# DDR3_Memory.net
KiCad netlist of a schematic drawn in Altium Designer
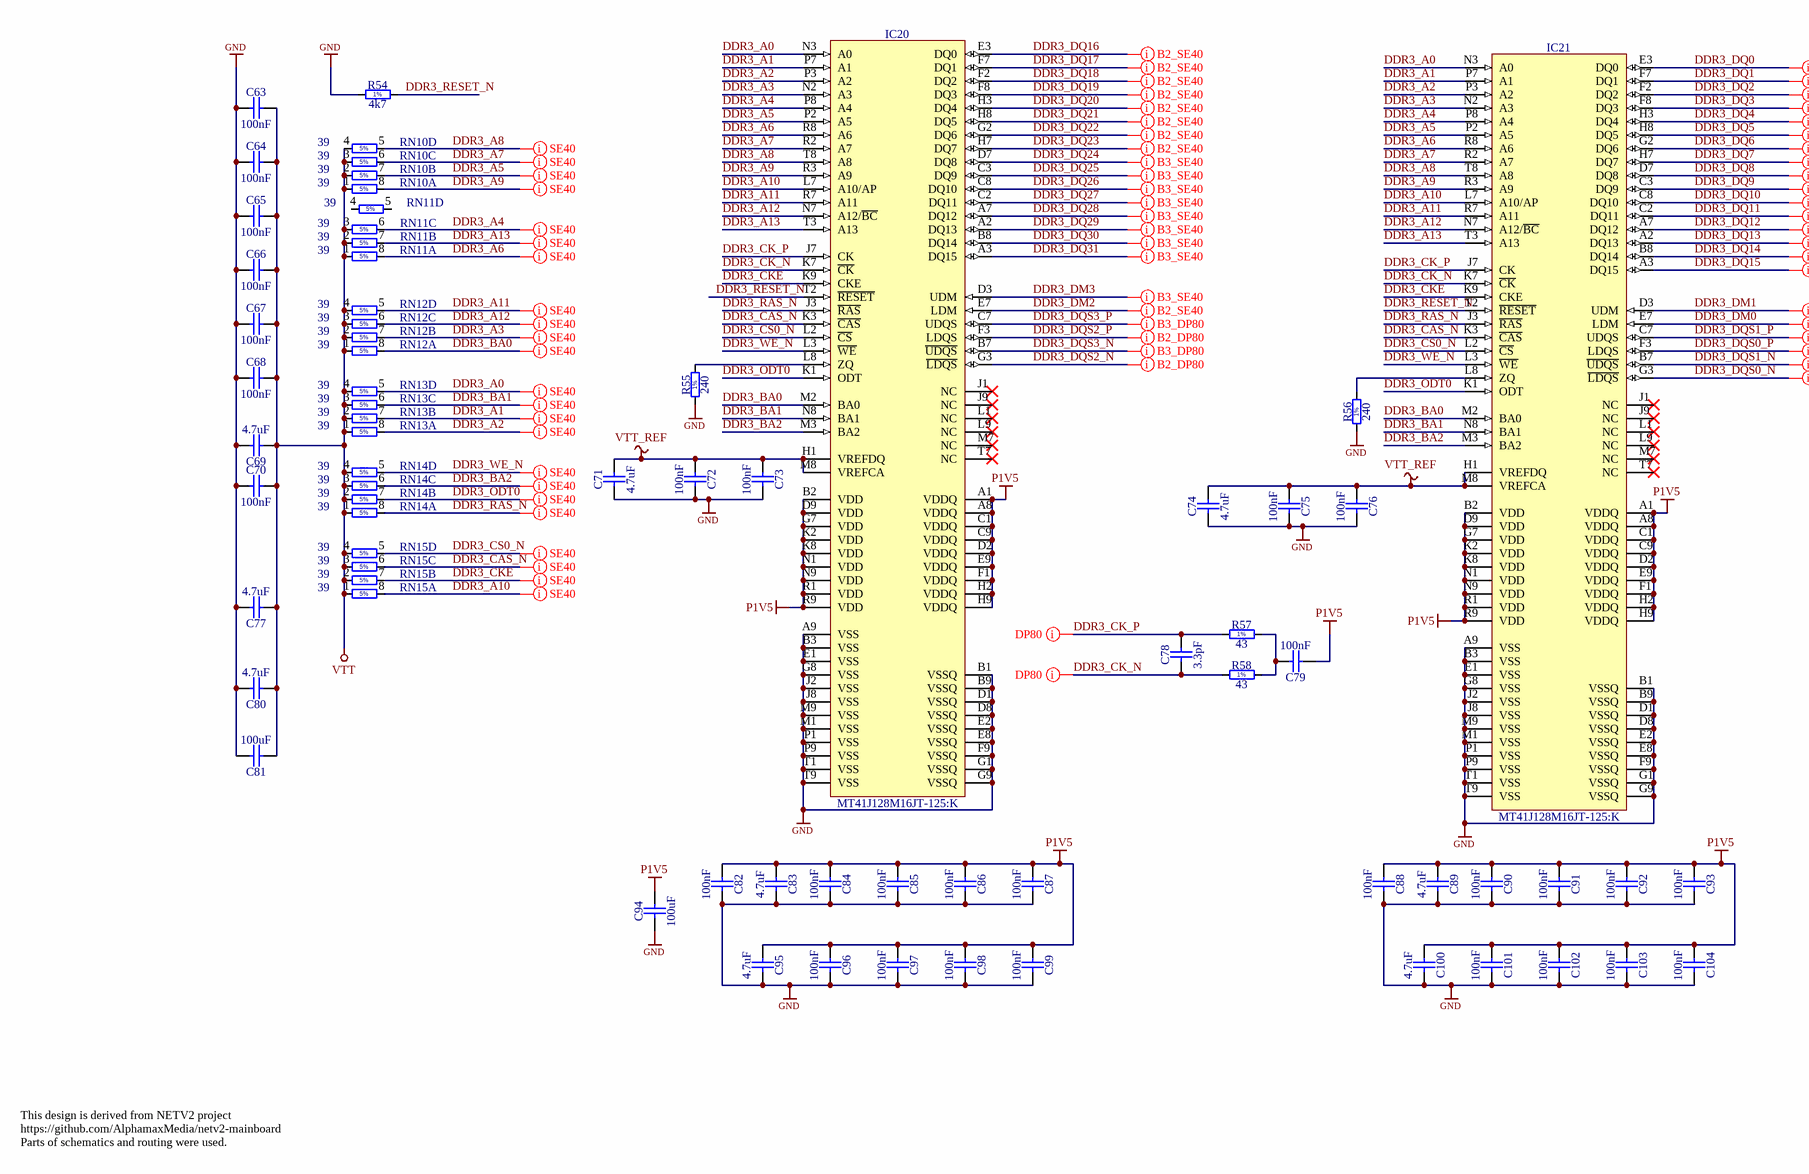
[diagram p0: DDR3_Memory.SchDoc]

(export (version "E")
  (design (tool "Eeschema 10.0.6"))
  (components
    (comp (ref "C63")
      (value "100nF")
      (footprint "CAPC0603X33N")
      (description "Non-polarised capacitor")
      (fields
        (field (name "PART NUMBER") "CC0201_100NF_6.3V_10%_X5R")
        (field (name "VOLTAGE") "6.3V")
        (field (name "AUTHOR") "CERN DEM JLC")
      )
      (libsource (lib "Capacitors") (part "Capacitor - non polarized"))
    )
    (comp (ref "C64")
      (value "100nF")
      (footprint "CAPC0603X33N")
      (description "Non-polarised capacitor")
      (fields
        (field (name "PART NUMBER") "CC0201_100NF_6.3V_10%_X5R")
        (field (name "VOLTAGE") "6.3V")
        (field (name "AUTHOR") "CERN DEM JLC")
      )
      (libsource (lib "Capacitors") (part "Capacitor - non polarized"))
    )
    (comp (ref "C65")
      (value "100nF")
      (footprint "CAPC0603X33N")
      (description "Non-polarised capacitor")
      (fields
        (field (name "PART NUMBER") "CC0201_100NF_6.3V_10%_X5R")
        (field (name "VOLTAGE") "6.3V")
        (field (name "AUTHOR") "CERN DEM JLC")
      )
      (libsource (lib "Capacitors") (part "Capacitor - non polarized"))
    )
    (comp (ref "C66")
      (value "100nF")
      (footprint "CAPC0603X33N")
      (description "Non-polarised capacitor")
      (fields
        (field (name "PART NUMBER") "CC0201_100NF_6.3V_10%_X5R")
        (field (name "VOLTAGE") "6.3V")
        (field (name "AUTHOR") "CERN DEM JLC")
      )
      (libsource (lib "Capacitors") (part "Capacitor - non polarized"))
    )
    (comp (ref "C67")
      (value "100nF")
      (footprint "CAPC0603X33N")
      (description "Non-polarised capacitor")
      (fields
        (field (name "PART NUMBER") "CC0201_100NF_6.3V_10%_X5R")
        (field (name "VOLTAGE") "6.3V")
        (field (name "AUTHOR") "CERN DEM JLC")
      )
      (libsource (lib "Capacitors") (part "Capacitor - non polarized"))
    )
    (comp (ref "C68")
      (value "100nF")
      (footprint "CAPC0603X33N")
      (description "Non-polarised capacitor")
      (fields
        (field (name "PART NUMBER") "CC0201_100NF_6.3V_10%_X5R")
        (field (name "VOLTAGE") "6.3V")
        (field (name "AUTHOR") "CERN DEM JLC")
      )
      (libsource (lib "Capacitors") (part "Capacitor - non polarized"))
    )
    (comp (ref "C69")
      (value "4.7uF")
      (footprint "CAPC1005X55N")
      (description "Non-polarised capacitor")
      (fields
        (field (name "PART NUMBER") "CC0402_4.7UF_6.3V_20%_X5R")
        (field (name "VOLTAGE") "6.3V")
        (field (name "AUTHOR") "CERN DEM JLC")
      )
      (libsource (lib "Capacitors") (part "Capacitor - non polarized"))
    )
    (comp (ref "C70")
      (value "100nF")
      (footprint "CAPC0603X33N")
      (description "Non-polarised capacitor")
      (fields
        (field (name "PART NUMBER") "CC0201_100NF_6.3V_10%_X5R")
        (field (name "VOLTAGE") "6.3V")
        (field (name "AUTHOR") "CERN DEM JLC")
      )
      (libsource (lib "Capacitors") (part "Capacitor - non polarized"))
    )
    (comp (ref "C71")
      (value "4.7uF")
      (footprint "CAPC1005X55N")
      (description "Non-polarised capacitor")
      (fields
        (field (name "PART NUMBER") "CC0402_4.7UF_6.3V_20%_X5R")
        (field (name "VOLTAGE") "6.3V")
        (field (name "AUTHOR") "CERN DEM JLC")
      )
      (libsource (lib "Capacitors") (part "Capacitor - non polarized"))
    )
    (comp (ref "C72")
      (value "100nF")
      (footprint "CAPC0603X33N")
      (description "Non-polarised capacitor")
      (fields
        (field (name "PART NUMBER") "CC0201_100NF_6.3V_10%_X5R")
        (field (name "VOLTAGE") "6.3V")
        (field (name "AUTHOR") "CERN DEM JLC")
      )
      (libsource (lib "Capacitors") (part "Capacitor - non polarized"))
    )
    (comp (ref "C73")
      (value "100nF")
      (footprint "CAPC0603X33N")
      (description "Non-polarised capacitor")
      (fields
        (field (name "PART NUMBER") "CC0201_100NF_6.3V_10%_X5R")
        (field (name "VOLTAGE") "6.3V")
        (field (name "AUTHOR") "CERN DEM JLC")
      )
      (libsource (lib "Capacitors") (part "Capacitor - non polarized"))
    )
    (comp (ref "C74")
      (value "4.7uF")
      (footprint "CAPC1005X55N")
      (description "Non-polarised capacitor")
      (fields
        (field (name "PART NUMBER") "CC0402_4.7UF_6.3V_20%_X5R")
        (field (name "VOLTAGE") "6.3V")
        (field (name "AUTHOR") "CERN DEM JLC")
      )
      (libsource (lib "Capacitors") (part "Capacitor - non polarized"))
    )
    (comp (ref "C75")
      (value "100nF")
      (footprint "CAPC0603X33N")
      (description "Non-polarised capacitor")
      (fields
        (field (name "PART NUMBER") "CC0201_100NF_6.3V_10%_X5R")
        (field (name "VOLTAGE") "6.3V")
        (field (name "AUTHOR") "CERN DEM JLC")
      )
      (libsource (lib "Capacitors") (part "Capacitor - non polarized"))
    )
    (comp (ref "C76")
      (value "100nF")
      (footprint "CAPC0603X33N")
      (description "Non-polarised capacitor")
      (fields
        (field (name "PART NUMBER") "CC0201_100NF_6.3V_10%_X5R")
        (field (name "VOLTAGE") "6.3V")
        (field (name "AUTHOR") "CERN DEM JLC")
      )
      (libsource (lib "Capacitors") (part "Capacitor - non polarized"))
    )
    (comp (ref "C77")
      (value "4.7uF")
      (footprint "CAPC1005X55N")
      (description "Non-polarised capacitor")
      (fields
        (field (name "PART NUMBER") "CC0402_4.7UF_6.3V_20%_X5R")
        (field (name "VOLTAGE") "6.3V")
        (field (name "AUTHOR") "CERN DEM JLC")
      )
      (libsource (lib "Capacitors") (part "Capacitor - non polarized"))
    )
    (comp (ref "C78")
      (value "3.3pF")
      (footprint "CAPC1005X55N")
      (description "Non-polarised capacitor")
      (fields
        (field (name "PART NUMBER") "CC0402_3.3PF_50V_0.25PF_C0G")
        (field (name "VOLTAGE") "50V")
        (field (name "AUTHOR") "CERN DEM JLC")
      )
      (libsource (lib "Capacitors") (part "Capacitor - non polarized"))
    )
    (comp (ref "C79")
      (value "100nF")
      (footprint "CAPC0603X33N")
      (description "Non-polarised capacitor")
      (fields
        (field (name "PART NUMBER") "CC0201_100NF_6.3V_10%_X5R")
        (field (name "VOLTAGE") "6.3V")
        (field (name "AUTHOR") "CERN DEM JLC")
      )
      (libsource (lib "Capacitors") (part "Capacitor - non polarized"))
    )
    (comp (ref "C80")
      (value "4.7uF")
      (footprint "CAPC1005X55N")
      (description "Non-polarised capacitor")
      (fields
        (field (name "PART NUMBER") "CC0402_4.7UF_6.3V_20%_X5R")
        (field (name "VOLTAGE") "6.3V")
        (field (name "AUTHOR") "CERN DEM JLC")
      )
      (libsource (lib "Capacitors") (part "Capacitor - non polarized"))
    )
    (comp (ref "C81")
      (value "100uF")
      (footprint "CAPC3216X180N")
      (description "Non-polarised capacitor")
      (fields
        (field (name "PART NUMBER") "CC1206_100UF_6.3V_20%_X5R")
        (field (name "VOLTAGE") "6.3V")
        (field (name "AUTHOR") "CERN DEM JLC")
      )
      (libsource (lib "Capacitors") (part "Capacitor - non polarized"))
    )
    (comp (ref "C82")
      (value "100nF")
      (footprint "CAPC0603X33N")
      (description "Non-polarised capacitor")
      (fields
        (field (name "PART NUMBER") "CC0201_100NF_6.3V_10%_X5R")
        (field (name "VOLTAGE") "6.3V")
        (field (name "AUTHOR") "CERN DEM JLC")
      )
      (libsource (lib "Capacitors") (part "Capacitor - non polarized"))
    )
    (comp (ref "C83")
      (value "4.7uF")
      (footprint "CAPC1005X55N")
      (description "Non-polarised capacitor")
      (fields
        (field (name "PART NUMBER") "CC0402_4.7UF_6.3V_20%_X5R")
        (field (name "VOLTAGE") "6.3V")
        (field (name "AUTHOR") "CERN DEM JLC")
      )
      (libsource (lib "Capacitors") (part "Capacitor - non polarized"))
    )
    (comp (ref "C84")
      (value "100nF")
      (footprint "CAPC0603X33N")
      (description "Non-polarised capacitor")
      (fields
        (field (name "PART NUMBER") "CC0201_100NF_6.3V_10%_X5R")
        (field (name "VOLTAGE") "6.3V")
        (field (name "AUTHOR") "CERN DEM JLC")
      )
      (libsource (lib "Capacitors") (part "Capacitor - non polarized"))
    )
    (comp (ref "C85")
      (value "100nF")
      (footprint "CAPC0603X33N")
      (description "Non-polarised capacitor")
      (fields
        (field (name "PART NUMBER") "CC0201_100NF_6.3V_10%_X5R")
        (field (name "VOLTAGE") "6.3V")
        (field (name "AUTHOR") "CERN DEM JLC")
      )
      (libsource (lib "Capacitors") (part "Capacitor - non polarized"))
    )
    (comp (ref "C86")
      (value "100nF")
      (footprint "CAPC0603X33N")
      (description "Non-polarised capacitor")
      (fields
        (field (name "PART NUMBER") "CC0201_100NF_6.3V_10%_X5R")
        (field (name "VOLTAGE") "6.3V")
        (field (name "AUTHOR") "CERN DEM JLC")
      )
      (libsource (lib "Capacitors") (part "Capacitor - non polarized"))
    )
    (comp (ref "C87")
      (value "100nF")
      (footprint "CAPC0603X33N")
      (description "Non-polarised capacitor")
      (fields
        (field (name "PART NUMBER") "CC0201_100NF_6.3V_10%_X5R")
        (field (name "VOLTAGE") "6.3V")
        (field (name "AUTHOR") "CERN DEM JLC")
      )
      (libsource (lib "Capacitors") (part "Capacitor - non polarized"))
    )
    (comp (ref "C88")
      (value "100nF")
      (footprint "CAPC0603X33N")
      (description "Non-polarised capacitor")
      (fields
        (field (name "PART NUMBER") "CC0201_100NF_6.3V_10%_X5R")
        (field (name "VOLTAGE") "6.3V")
        (field (name "AUTHOR") "CERN DEM JLC")
      )
      (libsource (lib "Capacitors") (part "Capacitor - non polarized"))
    )
    (comp (ref "C89")
      (value "4.7uF")
      (footprint "CAPC1005X55N")
      (description "Non-polarised capacitor")
      (fields
        (field (name "PART NUMBER") "CC0402_4.7UF_6.3V_20%_X5R")
        (field (name "VOLTAGE") "6.3V")
        (field (name "AUTHOR") "CERN DEM JLC")
      )
      (libsource (lib "Capacitors") (part "Capacitor - non polarized"))
    )
    (comp (ref "C90")
      (value "100nF")
      (footprint "CAPC0603X33N")
      (description "Non-polarised capacitor")
      (fields
        (field (name "PART NUMBER") "CC0201_100NF_6.3V_10%_X5R")
        (field (name "VOLTAGE") "6.3V")
        (field (name "AUTHOR") "CERN DEM JLC")
      )
      (libsource (lib "Capacitors") (part "Capacitor - non polarized"))
    )
    (comp (ref "C91")
      (value "100nF")
      (footprint "CAPC0603X33N")
      (description "Non-polarised capacitor")
      (fields
        (field (name "PART NUMBER") "CC0201_100NF_6.3V_10%_X5R")
        (field (name "VOLTAGE") "6.3V")
        (field (name "AUTHOR") "CERN DEM JLC")
      )
      (libsource (lib "Capacitors") (part "Capacitor - non polarized"))
    )
    (comp (ref "C92")
      (value "100nF")
      (footprint "CAPC0603X33N")
      (description "Non-polarised capacitor")
      (fields
        (field (name "PART NUMBER") "CC0201_100NF_6.3V_10%_X5R")
        (field (name "VOLTAGE") "6.3V")
        (field (name "AUTHOR") "CERN DEM JLC")
      )
      (libsource (lib "Capacitors") (part "Capacitor - non polarized"))
    )
    (comp (ref "C93")
      (value "100nF")
      (footprint "CAPC0603X33N")
      (description "Non-polarised capacitor")
      (fields
        (field (name "PART NUMBER") "CC0201_100NF_6.3V_10%_X5R")
        (field (name "VOLTAGE") "6.3V")
        (field (name "AUTHOR") "CERN DEM JLC")
      )
      (libsource (lib "Capacitors") (part "Capacitor - non polarized"))
    )
    (comp (ref "C94")
      (value "100uF")
      (footprint "CAPC3216X180N")
      (description "Non-polarised capacitor")
      (fields
        (field (name "PART NUMBER") "CC1206_100UF_6.3V_20%_X5R")
        (field (name "VOLTAGE") "6.3V")
        (field (name "AUTHOR") "CERN DEM JLC")
      )
      (libsource (lib "Capacitors") (part "Capacitor - non polarized"))
    )
    (comp (ref "C95")
      (value "4.7uF")
      (footprint "CAPC1005X55N")
      (description "Non-polarised capacitor")
      (fields
        (field (name "PART NUMBER") "CC0402_4.7UF_6.3V_20%_X5R")
        (field (name "VOLTAGE") "6.3V")
        (field (name "AUTHOR") "CERN DEM JLC")
      )
      (libsource (lib "Capacitors") (part "Capacitor - non polarized"))
    )
    (comp (ref "C96")
      (value "100nF")
      (footprint "CAPC0603X33N")
      (description "Non-polarised capacitor")
      (fields
        (field (name "PART NUMBER") "CC0201_100NF_6.3V_10%_X5R")
        (field (name "VOLTAGE") "6.3V")
        (field (name "AUTHOR") "CERN DEM JLC")
      )
      (libsource (lib "Capacitors") (part "Capacitor - non polarized"))
    )
    (comp (ref "C97")
      (value "100nF")
      (footprint "CAPC0603X33N")
      (description "Non-polarised capacitor")
      (fields
        (field (name "PART NUMBER") "CC0201_100NF_6.3V_10%_X5R")
        (field (name "VOLTAGE") "6.3V")
        (field (name "AUTHOR") "CERN DEM JLC")
      )
      (libsource (lib "Capacitors") (part "Capacitor - non polarized"))
    )
    (comp (ref "C98")
      (value "100nF")
      (footprint "CAPC0603X33N")
      (description "Non-polarised capacitor")
      (fields
        (field (name "PART NUMBER") "CC0201_100NF_6.3V_10%_X5R")
        (field (name "VOLTAGE") "6.3V")
        (field (name "AUTHOR") "CERN DEM JLC")
      )
      (libsource (lib "Capacitors") (part "Capacitor - non polarized"))
    )
    (comp (ref "C99")
      (value "100nF")
      (footprint "CAPC0603X33N")
      (description "Non-polarised capacitor")
      (fields
        (field (name "PART NUMBER") "CC0201_100NF_6.3V_10%_X5R")
        (field (name "VOLTAGE") "6.3V")
        (field (name "AUTHOR") "CERN DEM JLC")
      )
      (libsource (lib "Capacitors") (part "Capacitor - non polarized"))
    )
    (comp (ref "C100")
      (value "4.7uF")
      (footprint "CAPC1005X55N")
      (description "Non-polarised capacitor")
      (fields
        (field (name "PART NUMBER") "CC0402_4.7UF_6.3V_20%_X5R")
        (field (name "VOLTAGE") "6.3V")
        (field (name "AUTHOR") "CERN DEM JLC")
      )
      (libsource (lib "Capacitors") (part "Capacitor - non polarized"))
    )
    (comp (ref "C101")
      (value "100nF")
      (footprint "CAPC0603X33N")
      (description "Non-polarised capacitor")
      (fields
        (field (name "PART NUMBER") "CC0201_100NF_6.3V_10%_X5R")
        (field (name "VOLTAGE") "6.3V")
        (field (name "AUTHOR") "CERN DEM JLC")
      )
      (libsource (lib "Capacitors") (part "Capacitor - non polarized"))
    )
    (comp (ref "C102")
      (value "100nF")
      (footprint "CAPC0603X33N")
      (description "Non-polarised capacitor")
      (fields
        (field (name "PART NUMBER") "CC0201_100NF_6.3V_10%_X5R")
        (field (name "VOLTAGE") "6.3V")
        (field (name "AUTHOR") "CERN DEM JLC")
      )
      (libsource (lib "Capacitors") (part "Capacitor - non polarized"))
    )
    (comp (ref "C103")
      (value "100nF")
      (footprint "CAPC0603X33N")
      (description "Non-polarised capacitor")
      (fields
        (field (name "PART NUMBER") "CC0201_100NF_6.3V_10%_X5R")
        (field (name "VOLTAGE") "6.3V")
        (field (name "AUTHOR") "CERN DEM JLC")
      )
      (libsource (lib "Capacitors") (part "Capacitor - non polarized"))
    )
    (comp (ref "C104")
      (value "100nF")
      (footprint "CAPC0603X33N")
      (description "Non-polarised capacitor")
      (fields
        (field (name "PART NUMBER") "CC0201_100NF_6.3V_10%_X5R")
        (field (name "VOLTAGE") "6.3V")
        (field (name "AUTHOR") "CERN DEM JLC")
      )
      (libsource (lib "Capacitors") (part "Capacitor - non polarized"))
    )
    (comp (ref "IC20")
      (value "MT41J128M16JT-125:K")
      (footprint "BGA96C80P9X16_900X1400X120")
      (description "16 Meg x 16 x 8 Banks DDR3 SDRAM")
      (fields (field (name "MANUFACTURER") "MICRON TECHNOLOGY") (field (name "AUTHOR") "CERN DEM JLC"))
      (libsource (lib "ICs And Semiconductors") (part "MT41J128M16HA"))
    )
    (comp (ref "IC21")
      (value "MT41J128M16JT-125:K")
      (footprint "BGA96C80P9X16_900X1400X120")
      (description "16 Meg x 16 x 8 Banks DDR3 SDRAM")
      (fields (field (name "MANUFACTURER") "MICRON TECHNOLOGY") (field (name "AUTHOR") "CERN DEM JLC"))
      (libsource (lib "ICs And Semiconductors") (part "MT41J128M16HA"))
    )
    (comp (ref "R54")
      (value "4k7")
      (footprint "RESC1005X40N")
      (description "Resistor - 1%")
      (fields
        (field (name "PART NUMBER") "R0402_4K7_1%_0.0625W_100PPM")
        (field (name "POWER") "0.0625W")
        (field (name "AUTHOR") "CERN DEM JLC")
      )
      (libsource (lib "Resistors") (part "Resistor - 1%"))
    )
    (comp (ref "R55")
      (value "240")
      (footprint "RESC1005X40N")
      (description "Resistor - 1%")
      (fields
        (field (name "PART NUMBER") "R0402_240R_1%_0.0625W_100PPM")
        (field (name "POWER") "0.0625W")
        (field (name "AUTHOR") "CERN DEM JLC")
      )
      (libsource (lib "Resistors") (part "Resistor - 1%"))
    )
    (comp (ref "R56")
      (value "240")
      (footprint "RESC1005X40N")
      (description "Resistor - 1%")
      (fields
        (field (name "PART NUMBER") "R0402_240R_1%_0.0625W_100PPM")
        (field (name "POWER") "0.0625W")
        (field (name "AUTHOR") "CERN DEM JLC")
      )
      (libsource (lib "Resistors") (part "Resistor - 1%"))
    )
    (comp (ref "R57")
      (value "43")
      (footprint "RESC1005X40N")
      (description "Resistor - 1%")
      (fields
        (field (name "PART NUMBER") "R0402_43R_1%_0.0625W_100PPM")
        (field (name "POWER") "0.0625W")
        (field (name "AUTHOR") "CERN DEM JLC")
      )
      (libsource (lib "Resistors") (part "Resistor - 1%"))
    )
    (comp (ref "R58")
      (value "43")
      (footprint "RESC1005X40N")
      (description "Resistor - 1%")
      (fields
        (field (name "PART NUMBER") "R0402_43R_1%_0.0625W_100PPM")
        (field (name "POWER") "0.0625W")
        (field (name "AUTHOR") "CERN DEM JLC")
      )
      (libsource (lib "Resistors") (part "Resistor - 1%"))
    )
    (comp (ref "RN10")
      (value "39")
      (footprint "RN_YAGEO_YC124")
      (description "39R Resistor Network 4 Isolated Resistor 5%")
      (fields
        (field (name "PART NUMBER") "RN_10R_YAGEO_TC124-JR-0739RL")
        (field (name "POWER") "0.062W")
        (field (name "AUTHOR") "GK")
      )
      (libsource (lib "Passives_RC") (part "RES_RN_39R_YAGEO_TC124-JR-0739RL"))
    )
    (comp (ref "RN11")
      (value "39")
      (footprint "RN_YAGEO_YC124")
      (description "39R Resistor Network 4 Isolated Resistor 5%")
      (fields
        (field (name "PART NUMBER") "RN_10R_YAGEO_TC124-JR-0739RL")
        (field (name "POWER") "0.062W")
        (field (name "AUTHOR") "GK")
      )
      (libsource (lib "Passives_RC") (part "RES_RN_39R_YAGEO_TC124-JR-0739RL"))
    )
    (comp (ref "RN12")
      (value "39")
      (footprint "RN_YAGEO_YC124")
      (description "39R Resistor Network 4 Isolated Resistor 5%")
      (fields
        (field (name "PART NUMBER") "RN_10R_YAGEO_TC124-JR-0739RL")
        (field (name "POWER") "0.062W")
        (field (name "AUTHOR") "GK")
      )
      (libsource (lib "Passives_RC") (part "RES_RN_39R_YAGEO_TC124-JR-0739RL"))
    )
    (comp (ref "RN13")
      (value "39")
      (footprint "RN_YAGEO_YC124")
      (description "39R Resistor Network 4 Isolated Resistor 5%")
      (fields
        (field (name "PART NUMBER") "RN_10R_YAGEO_TC124-JR-0739RL")
        (field (name "POWER") "0.062W")
        (field (name "AUTHOR") "GK")
      )
      (libsource (lib "Passives_RC") (part "RES_RN_39R_YAGEO_TC124-JR-0739RL"))
    )
    (comp (ref "RN14")
      (value "39")
      (footprint "RN_YAGEO_YC124")
      (description "39R Resistor Network 4 Isolated Resistor 5%")
      (fields
        (field (name "PART NUMBER") "RN_10R_YAGEO_TC124-JR-0739RL")
        (field (name "POWER") "0.062W")
        (field (name "AUTHOR") "GK")
      )
      (libsource (lib "Passives_RC") (part "RES_RN_39R_YAGEO_TC124-JR-0739RL"))
    )
    (comp (ref "RN15")
      (value "39")
      (footprint "RN_YAGEO_YC124")
      (description "39R Resistor Network 4 Isolated Resistor 5%")
      (fields
        (field (name "PART NUMBER") "RN_10R_YAGEO_TC124-JR-0739RL")
        (field (name "POWER") "0.062W")
        (field (name "AUTHOR") "GK")
      )
      (libsource (lib "Passives_RC") (part "RES_RN_39R_YAGEO_TC124-JR-0739RL"))
    )
  )
  (nets
    (net (code "1") (name "/DDR3_A0") (class "Default")
      (node (ref "IC20") (pin "N3") (pinfunction "A0_N3") (pintype "input"))
      (node (ref "IC21") (pin "N3") (pinfunction "A0_N3") (pintype "input"))
      (node (ref "RN13") (pin "5") (pinfunction "5_5") (pintype "passive"))
    )
    (net (code "2") (name "/DDR3_A1") (class "Default")
      (node (ref "IC20") (pin "P7") (pinfunction "A1_P7") (pintype "input"))
      (node (ref "IC21") (pin "P7") (pinfunction "A1_P7") (pintype "input"))
      (node (ref "RN13") (pin "7") (pinfunction "7_7") (pintype "passive"))
    )
    (net (code "3") (name "/DDR3_A2") (class "Default")
      (node (ref "IC20") (pin "P3") (pinfunction "A2_P3") (pintype "input"))
      (node (ref "IC21") (pin "P3") (pinfunction "A2_P3") (pintype "input"))
      (node (ref "RN13") (pin "8") (pinfunction "8_8") (pintype "passive"))
    )
    (net (code "4") (name "/DDR3_A3") (class "Default")
      (node (ref "IC20") (pin "N2") (pinfunction "A3_N2") (pintype "input"))
      (node (ref "IC21") (pin "N2") (pinfunction "A3_N2") (pintype "input"))
      (node (ref "RN12") (pin "7") (pinfunction "7_7") (pintype "passive"))
    )
    (net (code "5") (name "/DDR3_A4") (class "Default")
      (node (ref "IC20") (pin "P8") (pinfunction "A4_P8") (pintype "input"))
      (node (ref "IC21") (pin "P8") (pinfunction "A4_P8") (pintype "input"))
      (node (ref "RN11") (pin "6") (pinfunction "6_6") (pintype "passive"))
    )
    (net (code "6") (name "/DDR3_A5") (class "Default")
      (node (ref "IC20") (pin "P2") (pinfunction "A5_P2") (pintype "input"))
      (node (ref "IC21") (pin "P2") (pinfunction "A5_P2") (pintype "input"))
      (node (ref "RN10") (pin "7") (pinfunction "7_7") (pintype "passive"))
    )
    (net (code "7") (name "/DDR3_A6") (class "Default")
      (node (ref "IC20") (pin "R8") (pinfunction "A6_R8") (pintype "input"))
      (node (ref "IC21") (pin "R8") (pinfunction "A6_R8") (pintype "input"))
      (node (ref "RN11") (pin "8") (pinfunction "8_8") (pintype "passive"))
    )
    (net (code "8") (name "/DDR3_A7") (class "Default")
      (node (ref "IC20") (pin "R2") (pinfunction "A7_R2") (pintype "input"))
      (node (ref "IC21") (pin "R2") (pinfunction "A7_R2") (pintype "input"))
      (node (ref "RN10") (pin "6") (pinfunction "6_6") (pintype "passive"))
    )
    (net (code "9") (name "/DDR3_A8") (class "Default")
      (node (ref "IC20") (pin "T8") (pinfunction "A8_T8") (pintype "input"))
      (node (ref "IC21") (pin "T8") (pinfunction "A8_T8") (pintype "input"))
      (node (ref "RN10") (pin "5") (pinfunction "5_5") (pintype "passive"))
    )
    (net (code "10") (name "/DDR3_A9") (class "Default")
      (node (ref "IC20") (pin "R3") (pinfunction "A9_R3") (pintype "input"))
      (node (ref "IC21") (pin "R3") (pinfunction "A9_R3") (pintype "input"))
      (node (ref "RN10") (pin "8") (pinfunction "8_8") (pintype "passive"))
    )
    (net (code "11") (name "/DDR3_A10") (class "Default")
      (node (ref "IC20") (pin "L7") (pinfunction "A10/AP_L7") (pintype "input"))
      (node (ref "IC21") (pin "L7") (pinfunction "A10/AP_L7") (pintype "input"))
      (node (ref "RN15") (pin "8") (pinfunction "8_8") (pintype "passive"))
    )
    (net (code "12") (name "/DDR3_A11") (class "Default")
      (node (ref "IC20") (pin "R7") (pinfunction "A11_R7") (pintype "input"))
      (node (ref "IC21") (pin "R7") (pinfunction "A11_R7") (pintype "input"))
      (node (ref "RN12") (pin "5") (pinfunction "5_5") (pintype "passive"))
    )
    (net (code "13") (name "/DDR3_A12") (class "Default")
      (node (ref "IC20") (pin "N7") (pinfunction "A12/~{BC}_N7") (pintype "input"))
      (node (ref "IC21") (pin "N7") (pinfunction "A12/~{BC}_N7") (pintype "input"))
      (node (ref "RN12") (pin "6") (pinfunction "6_6") (pintype "passive"))
    )
    (net (code "14") (name "/DDR3_A13") (class "Default")
      (node (ref "IC20") (pin "T3") (pinfunction "A13_T3") (pintype "input"))
      (node (ref "IC21") (pin "T3") (pinfunction "A13_T3") (pintype "input"))
      (node (ref "RN11") (pin "7") (pinfunction "7_7") (pintype "passive"))
    )
    (net (code "15") (name "/DDR3_BA0") (class "Default")
      (node (ref "IC20") (pin "M2") (pinfunction "BA0_M2") (pintype "input"))
      (node (ref "IC21") (pin "M2") (pinfunction "BA0_M2") (pintype "input"))
      (node (ref "RN12") (pin "8") (pinfunction "8_8") (pintype "passive"))
    )
    (net (code "16") (name "/DDR3_BA1") (class "Default")
      (node (ref "IC20") (pin "N8") (pinfunction "BA1_N8") (pintype "input"))
      (node (ref "IC21") (pin "N8") (pinfunction "BA1_N8") (pintype "input"))
      (node (ref "RN13") (pin "6") (pinfunction "6_6") (pintype "passive"))
    )
    (net (code "17") (name "/DDR3_BA2") (class "Default")
      (node (ref "IC20") (pin "M3") (pinfunction "BA2_M3") (pintype "input"))
      (node (ref "IC21") (pin "M3") (pinfunction "BA2_M3") (pintype "input"))
      (node (ref "RN14") (pin "6") (pinfunction "6_6") (pintype "passive"))
    )
    (net (code "18") (name "/DDR3_CAS_N") (class "Default")
      (node (ref "IC20") (pin "K3") (pinfunction "~{CAS}_K3") (pintype "input"))
      (node (ref "IC21") (pin "K3") (pinfunction "~{CAS}_K3") (pintype "input"))
      (node (ref "RN15") (pin "6") (pinfunction "6_6") (pintype "passive"))
    )
    (net (code "19") (name "/DDR3_CKE") (class "Default")
      (node (ref "IC20") (pin "K9") (pinfunction "CKE_K9") (pintype "input"))
      (node (ref "IC21") (pin "K9") (pinfunction "CKE_K9") (pintype "input"))
      (node (ref "RN15") (pin "7") (pinfunction "7_7") (pintype "passive"))
    )
    (net (code "20") (name "/DDR3_CK_N") (class "Default")
      (node (ref "C78") (pin "1") (pinfunction "1_1") (pintype "passive"))
      (node (ref "IC20") (pin "K7") (pinfunction "~{CK}_K7") (pintype "input"))
      (node (ref "IC21") (pin "K7") (pinfunction "~{CK}_K7") (pintype "input"))
      (node (ref "R58") (pin "1") (pinfunction "1_1") (pintype "passive"))
    )
    (net (code "21") (name "/DDR3_CK_P") (class "Default")
      (node (ref "C78") (pin "2") (pinfunction "2_2") (pintype "passive"))
      (node (ref "IC20") (pin "J7") (pinfunction "CK_J7") (pintype "input"))
      (node (ref "IC21") (pin "J7") (pinfunction "CK_J7") (pintype "input"))
      (node (ref "R57") (pin "1") (pinfunction "1_1") (pintype "passive"))
    )
    (net (code "22") (name "/DDR3_CS0_N") (class "Default")
      (node (ref "IC20") (pin "L2") (pinfunction "~{CS}_L2") (pintype "input"))
      (node (ref "IC21") (pin "L2") (pinfunction "~{CS}_L2") (pintype "input"))
      (node (ref "RN15") (pin "5") (pinfunction "5_5") (pintype "passive"))
    )
    (net (code "23") (name "/DDR3_DM0") (class "Default")
      (node (ref "IC21") (pin "E7") (pinfunction "LDM_E7") (pintype "input"))
    )
    (net (code "24") (name "/DDR3_DM1") (class "Default")
      (node (ref "IC21") (pin "D3") (pinfunction "UDM_D3") (pintype "input"))
    )
    (net (code "25") (name "/DDR3_DM2") (class "Default")
      (node (ref "IC20") (pin "E7") (pinfunction "LDM_E7") (pintype "input"))
    )
    (net (code "26") (name "/DDR3_DM3") (class "Default")
      (node (ref "IC20") (pin "D3") (pinfunction "UDM_D3") (pintype "input"))
    )
    (net (code "27") (name "/DDR3_DQ0") (class "Default")
      (node (ref "IC21") (pin "E3") (pinfunction "DQ0_E3") (pintype "bidirectional"))
    )
    (net (code "28") (name "/DDR3_DQ1") (class "Default")
      (node (ref "IC21") (pin "F7") (pinfunction "DQ1_F7") (pintype "bidirectional"))
    )
    (net (code "29") (name "/DDR3_DQ2") (class "Default")
      (node (ref "IC21") (pin "F2") (pinfunction "DQ2_F2") (pintype "bidirectional"))
    )
    (net (code "30") (name "/DDR3_DQ3") (class "Default")
      (node (ref "IC21") (pin "F8") (pinfunction "DQ3_F8") (pintype "bidirectional"))
    )
    (net (code "31") (name "/DDR3_DQ4") (class "Default")
      (node (ref "IC21") (pin "H3") (pinfunction "DQ4_H3") (pintype "bidirectional"))
    )
    (net (code "32") (name "/DDR3_DQ5") (class "Default")
      (node (ref "IC21") (pin "H8") (pinfunction "DQ5_H8") (pintype "bidirectional"))
    )
    (net (code "33") (name "/DDR3_DQ6") (class "Default")
      (node (ref "IC21") (pin "G2") (pinfunction "DQ6_G2") (pintype "bidirectional"))
    )
    (net (code "34") (name "/DDR3_DQ7") (class "Default")
      (node (ref "IC21") (pin "H7") (pinfunction "DQ7_H7") (pintype "bidirectional"))
    )
    (net (code "35") (name "/DDR3_DQ8") (class "Default")
      (node (ref "IC21") (pin "D7") (pinfunction "DQ8_D7") (pintype "bidirectional"))
    )
    (net (code "36") (name "/DDR3_DQ9") (class "Default")
      (node (ref "IC21") (pin "C3") (pinfunction "DQ9_C3") (pintype "bidirectional"))
    )
    (net (code "37") (name "/DDR3_DQ10") (class "Default")
      (node (ref "IC21") (pin "C8") (pinfunction "DQ10_C8") (pintype "bidirectional"))
    )
    (net (code "38") (name "/DDR3_DQ11") (class "Default")
      (node (ref "IC21") (pin "C2") (pinfunction "DQ11_C2") (pintype "bidirectional"))
    )
    (net (code "39") (name "/DDR3_DQ12") (class "Default")
      (node (ref "IC21") (pin "A7") (pinfunction "DQ12_A7") (pintype "bidirectional"))
    )
    (net (code "40") (name "/DDR3_DQ13") (class "Default")
      (node (ref "IC21") (pin "A2") (pinfunction "DQ13_A2") (pintype "bidirectional"))
    )
    (net (code "41") (name "/DDR3_DQ14") (class "Default")
      (node (ref "IC21") (pin "B8") (pinfunction "DQ14_B8") (pintype "bidirectional"))
    )
    (net (code "42") (name "/DDR3_DQ15") (class "Default")
      (node (ref "IC21") (pin "A3") (pinfunction "DQ15_A3") (pintype "bidirectional"))
    )
    (net (code "43") (name "/DDR3_DQ16") (class "Default")
      (node (ref "IC20") (pin "E3") (pinfunction "DQ0_E3") (pintype "bidirectional"))
    )
    (net (code "44") (name "/DDR3_DQ17") (class "Default")
      (node (ref "IC20") (pin "F7") (pinfunction "DQ1_F7") (pintype "bidirectional"))
    )
    (net (code "45") (name "/DDR3_DQ18") (class "Default")
      (node (ref "IC20") (pin "F2") (pinfunction "DQ2_F2") (pintype "bidirectional"))
    )
    (net (code "46") (name "/DDR3_DQ19") (class "Default")
      (node (ref "IC20") (pin "F8") (pinfunction "DQ3_F8") (pintype "bidirectional"))
    )
    (net (code "47") (name "/DDR3_DQ20") (class "Default")
      (node (ref "IC20") (pin "H3") (pinfunction "DQ4_H3") (pintype "bidirectional"))
    )
    (net (code "48") (name "/DDR3_DQ21") (class "Default")
      (node (ref "IC20") (pin "H8") (pinfunction "DQ5_H8") (pintype "bidirectional"))
    )
    (net (code "49") (name "/DDR3_DQ22") (class "Default")
      (node (ref "IC20") (pin "G2") (pinfunction "DQ6_G2") (pintype "bidirectional"))
    )
    (net (code "50") (name "/DDR3_DQ23") (class "Default")
      (node (ref "IC20") (pin "H7") (pinfunction "DQ7_H7") (pintype "bidirectional"))
    )
    (net (code "51") (name "/DDR3_DQ24") (class "Default")
      (node (ref "IC20") (pin "D7") (pinfunction "DQ8_D7") (pintype "bidirectional"))
    )
    (net (code "52") (name "/DDR3_DQ25") (class "Default")
      (node (ref "IC20") (pin "C3") (pinfunction "DQ9_C3") (pintype "bidirectional"))
    )
    (net (code "53") (name "/DDR3_DQ26") (class "Default")
      (node (ref "IC20") (pin "C8") (pinfunction "DQ10_C8") (pintype "bidirectional"))
    )
    (net (code "54") (name "/DDR3_DQ27") (class "Default")
      (node (ref "IC20") (pin "C2") (pinfunction "DQ11_C2") (pintype "bidirectional"))
    )
    (net (code "55") (name "/DDR3_DQ28") (class "Default")
      (node (ref "IC20") (pin "A7") (pinfunction "DQ12_A7") (pintype "bidirectional"))
    )
    (net (code "56") (name "/DDR3_DQ29") (class "Default")
      (node (ref "IC20") (pin "A2") (pinfunction "DQ13_A2") (pintype "bidirectional"))
    )
    (net (code "57") (name "/DDR3_DQ30") (class "Default")
      (node (ref "IC20") (pin "B8") (pinfunction "DQ14_B8") (pintype "bidirectional"))
    )
    (net (code "58") (name "/DDR3_DQ31") (class "Default")
      (node (ref "IC20") (pin "A3") (pinfunction "DQ15_A3") (pintype "bidirectional"))
    )
    (net (code "59") (name "/DDR3_DQS0_N") (class "Default")
      (node (ref "IC21") (pin "G3") (pinfunction "~{LDQS}_G3") (pintype "bidirectional"))
    )
    (net (code "60") (name "/DDR3_DQS0_P") (class "Default")
      (node (ref "IC21") (pin "F3") (pinfunction "LDQS_F3") (pintype "bidirectional"))
    )
    (net (code "61") (name "/DDR3_DQS1_N") (class "Default")
      (node (ref "IC21") (pin "B7") (pinfunction "~{UDQS}_B7") (pintype "bidirectional"))
    )
    (net (code "62") (name "/DDR3_DQS1_P") (class "Default")
      (node (ref "IC21") (pin "C7") (pinfunction "UDQS_C7") (pintype "bidirectional"))
    )
    (net (code "63") (name "/DDR3_DQS2_N") (class "Default")
      (node (ref "IC20") (pin "G3") (pinfunction "~{LDQS}_G3") (pintype "bidirectional"))
    )
    (net (code "64") (name "/DDR3_DQS2_P") (class "Default")
      (node (ref "IC20") (pin "F3") (pinfunction "LDQS_F3") (pintype "bidirectional"))
    )
    (net (code "65") (name "/DDR3_DQS3_N") (class "Default")
      (node (ref "IC20") (pin "B7") (pinfunction "~{UDQS}_B7") (pintype "bidirectional"))
    )
    (net (code "66") (name "/DDR3_DQS3_P") (class "Default")
      (node (ref "IC20") (pin "C7") (pinfunction "UDQS_C7") (pintype "bidirectional"))
    )
    (net (code "67") (name "/DDR3_ODT0") (class "Default")
      (node (ref "IC20") (pin "K1") (pinfunction "ODT_K1") (pintype "input"))
      (node (ref "IC21") (pin "K1") (pinfunction "ODT_K1") (pintype "input"))
      (node (ref "RN14") (pin "7") (pinfunction "7_7") (pintype "passive"))
    )
    (net (code "68") (name "/DDR3_RAS_N") (class "Default")
      (node (ref "IC20") (pin "J3") (pinfunction "~{RAS}_J3") (pintype "input"))
      (node (ref "IC21") (pin "J3") (pinfunction "~{RAS}_J3") (pintype "input"))
      (node (ref "RN14") (pin "8") (pinfunction "8_8") (pintype "passive"))
    )
    (net (code "69") (name "/DDR3_RESET_N") (class "Default")
      (node (ref "IC20") (pin "T2") (pinfunction "~{RESET}_T2") (pintype "input"))
      (node (ref "IC21") (pin "T2") (pinfunction "~{RESET}_T2") (pintype "input"))
      (node (ref "R54") (pin "2") (pinfunction "2_2") (pintype "passive"))
    )
    (net (code "70") (name "/DDR3_WE_N") (class "Default")
      (node (ref "IC20") (pin "L3") (pinfunction "~{WE}_L3") (pintype "input"))
      (node (ref "IC21") (pin "L3") (pinfunction "~{WE}_L3") (pintype "input"))
      (node (ref "RN14") (pin "5") (pinfunction "5_5") (pintype "passive"))
    )
    (net (code "71") (name "GND") (class "Default")
      (node (ref "C100") (pin "2") (pinfunction "2_2") (pintype "passive"))
      (node (ref "C101") (pin "2") (pinfunction "2_2") (pintype "passive"))
      (node (ref "C102") (pin "2") (pinfunction "2_2") (pintype "passive"))
      (node (ref "C103") (pin "2") (pinfunction "2_2") (pintype "passive"))
      (node (ref "C104") (pin "2") (pinfunction "2_2") (pintype "passive"))
      (node (ref "C63") (pin "1") (pinfunction "1_1") (pintype "passive"))
      (node (ref "C64") (pin "1") (pinfunction "1_1") (pintype "passive"))
      (node (ref "C65") (pin "1") (pinfunction "1_1") (pintype "passive"))
      (node (ref "C66") (pin "1") (pinfunction "1_1") (pintype "passive"))
      (node (ref "C67") (pin "1") (pinfunction "1_1") (pintype "passive"))
      (node (ref "C68") (pin "1") (pinfunction "1_1") (pintype "passive"))
      (node (ref "C69") (pin "2") (pinfunction "2_2") (pintype "passive"))
      (node (ref "C70") (pin "1") (pinfunction "1_1") (pintype "passive"))
      (node (ref "C71") (pin "1") (pinfunction "1_1") (pintype "passive"))
      (node (ref "C72") (pin "2") (pinfunction "2_2") (pintype "passive"))
      (node (ref "C73") (pin "2") (pinfunction "2_2") (pintype "passive"))
      (node (ref "C74") (pin "1") (pinfunction "1_1") (pintype "passive"))
      (node (ref "C75") (pin "2") (pinfunction "2_2") (pintype "passive"))
      (node (ref "C76") (pin "2") (pinfunction "2_2") (pintype "passive"))
      (node (ref "C77") (pin "2") (pinfunction "2_2") (pintype "passive"))
      (node (ref "C80") (pin "2") (pinfunction "2_2") (pintype "passive"))
      (node (ref "C81") (pin "2") (pinfunction "2_2") (pintype "passive"))
      (node (ref "C82") (pin "2") (pinfunction "2_2") (pintype "passive"))
      (node (ref "C83") (pin "2") (pinfunction "2_2") (pintype "passive"))
      (node (ref "C84") (pin "2") (pinfunction "2_2") (pintype "passive"))
      (node (ref "C85") (pin "2") (pinfunction "2_2") (pintype "passive"))
      (node (ref "C86") (pin "2") (pinfunction "2_2") (pintype "passive"))
      (node (ref "C87") (pin "2") (pinfunction "2_2") (pintype "passive"))
      (node (ref "C88") (pin "2") (pinfunction "2_2") (pintype "passive"))
      (node (ref "C89") (pin "2") (pinfunction "2_2") (pintype "passive"))
      (node (ref "C90") (pin "2") (pinfunction "2_2") (pintype "passive"))
      (node (ref "C91") (pin "2") (pinfunction "2_2") (pintype "passive"))
      (node (ref "C92") (pin "2") (pinfunction "2_2") (pintype "passive"))
      (node (ref "C93") (pin "2") (pinfunction "2_2") (pintype "passive"))
      (node (ref "C94") (pin "1") (pinfunction "1_1") (pintype "passive"))
      (node (ref "C95") (pin "2") (pinfunction "2_2") (pintype "passive"))
      (node (ref "C96") (pin "2") (pinfunction "2_2") (pintype "passive"))
      (node (ref "C97") (pin "2") (pinfunction "2_2") (pintype "passive"))
      (node (ref "C98") (pin "2") (pinfunction "2_2") (pintype "passive"))
      (node (ref "C99") (pin "2") (pinfunction "2_2") (pintype "passive"))
      (node (ref "IC20") (pin "A9") (pinfunction "VSS_A9") (pintype "power_in"))
      (node (ref "IC20") (pin "B1") (pinfunction "VSSQ_B1") (pintype "power_in"))
      (node (ref "IC20") (pin "B3") (pinfunction "VSS_B3") (pintype "power_in"))
      (node (ref "IC20") (pin "B9") (pinfunction "VSSQ_B9") (pintype "power_in"))
      (node (ref "IC20") (pin "D1") (pinfunction "VSSQ_D1") (pintype "power_in"))
      (node (ref "IC20") (pin "D8") (pinfunction "VSSQ_D8") (pintype "power_in"))
      (node (ref "IC20") (pin "E1") (pinfunction "VSS_E1") (pintype "power_in"))
      (node (ref "IC20") (pin "E2") (pinfunction "VSSQ_E2") (pintype "power_in"))
      (node (ref "IC20") (pin "E8") (pinfunction "VSSQ_E8") (pintype "power_in"))
      (node (ref "IC20") (pin "F9") (pinfunction "VSSQ_F9") (pintype "power_in"))
      (node (ref "IC20") (pin "G1") (pinfunction "VSSQ_G1") (pintype "power_in"))
      (node (ref "IC20") (pin "G8") (pinfunction "VSS_G8") (pintype "power_in"))
      (node (ref "IC20") (pin "G9") (pinfunction "VSSQ_G9") (pintype "power_in"))
      (node (ref "IC20") (pin "J2") (pinfunction "VSS_J2") (pintype "power_in"))
      (node (ref "IC20") (pin "J8") (pinfunction "VSS_J8") (pintype "power_in"))
      (node (ref "IC20") (pin "M1") (pinfunction "VSS_M1") (pintype "power_in"))
      (node (ref "IC20") (pin "M9") (pinfunction "VSS_M9") (pintype "power_in"))
      (node (ref "IC20") (pin "P1") (pinfunction "VSS_P1") (pintype "power_in"))
      (node (ref "IC20") (pin "P9") (pinfunction "VSS_P9") (pintype "power_in"))
      (node (ref "IC20") (pin "T1") (pinfunction "VSS_T1") (pintype "power_in"))
      (node (ref "IC20") (pin "T9") (pinfunction "VSS_T9") (pintype "power_in"))
      (node (ref "IC21") (pin "A9") (pinfunction "VSS_A9") (pintype "power_in"))
      (node (ref "IC21") (pin "B1") (pinfunction "VSSQ_B1") (pintype "power_in"))
      (node (ref "IC21") (pin "B3") (pinfunction "VSS_B3") (pintype "power_in"))
      (node (ref "IC21") (pin "B9") (pinfunction "VSSQ_B9") (pintype "power_in"))
      (node (ref "IC21") (pin "D1") (pinfunction "VSSQ_D1") (pintype "power_in"))
      (node (ref "IC21") (pin "D8") (pinfunction "VSSQ_D8") (pintype "power_in"))
      (node (ref "IC21") (pin "E1") (pinfunction "VSS_E1") (pintype "power_in"))
      (node (ref "IC21") (pin "E2") (pinfunction "VSSQ_E2") (pintype "power_in"))
      (node (ref "IC21") (pin "E8") (pinfunction "VSSQ_E8") (pintype "power_in"))
      (node (ref "IC21") (pin "F9") (pinfunction "VSSQ_F9") (pintype "power_in"))
      (node (ref "IC21") (pin "G1") (pinfunction "VSSQ_G1") (pintype "power_in"))
      (node (ref "IC21") (pin "G8") (pinfunction "VSS_G8") (pintype "power_in"))
      (node (ref "IC21") (pin "G9") (pinfunction "VSSQ_G9") (pintype "power_in"))
      (node (ref "IC21") (pin "J2") (pinfunction "VSS_J2") (pintype "power_in"))
      (node (ref "IC21") (pin "J8") (pinfunction "VSS_J8") (pintype "power_in"))
      (node (ref "IC21") (pin "M1") (pinfunction "VSS_M1") (pintype "power_in"))
      (node (ref "IC21") (pin "M9") (pinfunction "VSS_M9") (pintype "power_in"))
      (node (ref "IC21") (pin "P1") (pinfunction "VSS_P1") (pintype "power_in"))
      (node (ref "IC21") (pin "P9") (pinfunction "VSS_P9") (pintype "power_in"))
      (node (ref "IC21") (pin "T1") (pinfunction "VSS_T1") (pintype "power_in"))
      (node (ref "IC21") (pin "T9") (pinfunction "VSS_T9") (pintype "power_in"))
      (node (ref "R54") (pin "1") (pinfunction "1_1") (pintype "passive"))
      (node (ref "R55") (pin "1") (pinfunction "1_1") (pintype "passive"))
      (node (ref "R56") (pin "1") (pinfunction "1_1") (pintype "passive"))
    )
    (net (code "72") (name "Net-(C79-Pad2)") (class "Default")
      (node (ref "C79") (pin "2") (pinfunction "2_2") (pintype "passive"))
      (node (ref "R57") (pin "2") (pinfunction "2_2") (pintype "passive"))
      (node (ref "R58") (pin "2") (pinfunction "2_2") (pintype "passive"))
    )
    (net (code "73") (name "Net-(IC20-ZQ)") (class "Default")
      (node (ref "IC20") (pin "L8") (pinfunction "ZQ_L8") (pintype "input"))
      (node (ref "R55") (pin "2") (pinfunction "2_2") (pintype "passive"))
    )
    (net (code "74") (name "Net-(IC21-ZQ)") (class "Default")
      (node (ref "IC21") (pin "L8") (pinfunction "ZQ_L8") (pintype "input"))
      (node (ref "R56") (pin "2") (pinfunction "2_2") (pintype "passive"))
    )
    (net (code "75") (name "P1V5") (class "Default")
      (node (ref "C100") (pin "1") (pinfunction "1_1") (pintype "passive"))
      (node (ref "C101") (pin "1") (pinfunction "1_1") (pintype "passive"))
      (node (ref "C102") (pin "1") (pinfunction "1_1") (pintype "passive"))
      (node (ref "C103") (pin "1") (pinfunction "1_1") (pintype "passive"))
      (node (ref "C104") (pin "1") (pinfunction "1_1") (pintype "passive"))
      (node (ref "C79") (pin "1") (pinfunction "1_1") (pintype "passive"))
      (node (ref "C82") (pin "1") (pinfunction "1_1") (pintype "passive"))
      (node (ref "C83") (pin "1") (pinfunction "1_1") (pintype "passive"))
      (node (ref "C84") (pin "1") (pinfunction "1_1") (pintype "passive"))
      (node (ref "C85") (pin "1") (pinfunction "1_1") (pintype "passive"))
      (node (ref "C86") (pin "1") (pinfunction "1_1") (pintype "passive"))
      (node (ref "C87") (pin "1") (pinfunction "1_1") (pintype "passive"))
      (node (ref "C88") (pin "1") (pinfunction "1_1") (pintype "passive"))
      (node (ref "C89") (pin "1") (pinfunction "1_1") (pintype "passive"))
      (node (ref "C90") (pin "1") (pinfunction "1_1") (pintype "passive"))
      (node (ref "C91") (pin "1") (pinfunction "1_1") (pintype "passive"))
      (node (ref "C92") (pin "1") (pinfunction "1_1") (pintype "passive"))
      (node (ref "C93") (pin "1") (pinfunction "1_1") (pintype "passive"))
      (node (ref "C94") (pin "2") (pinfunction "2_2") (pintype "passive"))
      (node (ref "C95") (pin "1") (pinfunction "1_1") (pintype "passive"))
      (node (ref "C96") (pin "1") (pinfunction "1_1") (pintype "passive"))
      (node (ref "C97") (pin "1") (pinfunction "1_1") (pintype "passive"))
      (node (ref "C98") (pin "1") (pinfunction "1_1") (pintype "passive"))
      (node (ref "C99") (pin "1") (pinfunction "1_1") (pintype "passive"))
      (node (ref "IC20") (pin "A1") (pinfunction "VDDQ_A1") (pintype "power_in"))
      (node (ref "IC20") (pin "A8") (pinfunction "VDDQ_A8") (pintype "power_in"))
      (node (ref "IC20") (pin "B2") (pinfunction "VDD_B2") (pintype "power_in"))
      (node (ref "IC20") (pin "C1") (pinfunction "VDDQ_C1") (pintype "power_in"))
      (node (ref "IC20") (pin "C9") (pinfunction "VDDQ_C9") (pintype "power_in"))
      (node (ref "IC20") (pin "D2") (pinfunction "VDDQ_D2") (pintype "power_in"))
      (node (ref "IC20") (pin "D9") (pinfunction "VDD_D9") (pintype "power_in"))
      (node (ref "IC20") (pin "E9") (pinfunction "VDDQ_E9") (pintype "power_in"))
      (node (ref "IC20") (pin "F1") (pinfunction "VDDQ_F1") (pintype "power_in"))
      (node (ref "IC20") (pin "G7") (pinfunction "VDD_G7") (pintype "power_in"))
      (node (ref "IC20") (pin "H2") (pinfunction "VDDQ_H2") (pintype "power_in"))
      (node (ref "IC20") (pin "H9") (pinfunction "VDDQ_H9") (pintype "power_in"))
      (node (ref "IC20") (pin "K2") (pinfunction "VDD_K2") (pintype "power_in"))
      (node (ref "IC20") (pin "K8") (pinfunction "VDD_K8") (pintype "power_in"))
      (node (ref "IC20") (pin "N1") (pinfunction "VDD_N1") (pintype "power_in"))
      (node (ref "IC20") (pin "N9") (pinfunction "VDD_N9") (pintype "power_in"))
      (node (ref "IC20") (pin "R1") (pinfunction "VDD_R1") (pintype "power_in"))
      (node (ref "IC20") (pin "R9") (pinfunction "VDD_R9") (pintype "power_in"))
      (node (ref "IC21") (pin "A1") (pinfunction "VDDQ_A1") (pintype "power_in"))
      (node (ref "IC21") (pin "A8") (pinfunction "VDDQ_A8") (pintype "power_in"))
      (node (ref "IC21") (pin "B2") (pinfunction "VDD_B2") (pintype "power_in"))
      (node (ref "IC21") (pin "C1") (pinfunction "VDDQ_C1") (pintype "power_in"))
      (node (ref "IC21") (pin "C9") (pinfunction "VDDQ_C9") (pintype "power_in"))
      (node (ref "IC21") (pin "D2") (pinfunction "VDDQ_D2") (pintype "power_in"))
      (node (ref "IC21") (pin "D9") (pinfunction "VDD_D9") (pintype "power_in"))
      (node (ref "IC21") (pin "E9") (pinfunction "VDDQ_E9") (pintype "power_in"))
      (node (ref "IC21") (pin "F1") (pinfunction "VDDQ_F1") (pintype "power_in"))
      (node (ref "IC21") (pin "G7") (pinfunction "VDD_G7") (pintype "power_in"))
      (node (ref "IC21") (pin "H2") (pinfunction "VDDQ_H2") (pintype "power_in"))
      (node (ref "IC21") (pin "H9") (pinfunction "VDDQ_H9") (pintype "power_in"))
      (node (ref "IC21") (pin "K2") (pinfunction "VDD_K2") (pintype "power_in"))
      (node (ref "IC21") (pin "K8") (pinfunction "VDD_K8") (pintype "power_in"))
      (node (ref "IC21") (pin "N1") (pinfunction "VDD_N1") (pintype "power_in"))
      (node (ref "IC21") (pin "N9") (pinfunction "VDD_N9") (pintype "power_in"))
      (node (ref "IC21") (pin "R1") (pinfunction "VDD_R1") (pintype "power_in"))
      (node (ref "IC21") (pin "R9") (pinfunction "VDD_R9") (pintype "power_in"))
    )
    (net (code "76") (name "VTT") (class "Default")
      (node (ref "C63") (pin "2") (pinfunction "2_2") (pintype "passive"))
      (node (ref "C64") (pin "2") (pinfunction "2_2") (pintype "passive"))
      (node (ref "C65") (pin "2") (pinfunction "2_2") (pintype "passive"))
      (node (ref "C66") (pin "2") (pinfunction "2_2") (pintype "passive"))
      (node (ref "C67") (pin "2") (pinfunction "2_2") (pintype "passive"))
      (node (ref "C68") (pin "2") (pinfunction "2_2") (pintype "passive"))
      (node (ref "C69") (pin "1") (pinfunction "1_1") (pintype "passive"))
      (node (ref "C70") (pin "2") (pinfunction "2_2") (pintype "passive"))
      (node (ref "C77") (pin "1") (pinfunction "1_1") (pintype "passive"))
      (node (ref "C80") (pin "1") (pinfunction "1_1") (pintype "passive"))
      (node (ref "C81") (pin "1") (pinfunction "1_1") (pintype "passive"))
      (node (ref "RN10") (pin "1") (pinfunction "1_1") (pintype "passive"))
      (node (ref "RN10") (pin "2") (pinfunction "2_2") (pintype "passive"))
      (node (ref "RN10") (pin "3") (pinfunction "3_3") (pintype "passive"))
      (node (ref "RN10") (pin "4") (pinfunction "4_4") (pintype "passive"))
      (node (ref "RN11") (pin "1") (pinfunction "1_1") (pintype "passive"))
      (node (ref "RN11") (pin "2") (pinfunction "2_2") (pintype "passive"))
      (node (ref "RN11") (pin "3") (pinfunction "3_3") (pintype "passive"))
      (node (ref "RN12") (pin "1") (pinfunction "1_1") (pintype "passive"))
      (node (ref "RN12") (pin "2") (pinfunction "2_2") (pintype "passive"))
      (node (ref "RN12") (pin "3") (pinfunction "3_3") (pintype "passive"))
      (node (ref "RN12") (pin "4") (pinfunction "4_4") (pintype "passive"))
      (node (ref "RN13") (pin "1") (pinfunction "1_1") (pintype "passive"))
      (node (ref "RN13") (pin "2") (pinfunction "2_2") (pintype "passive"))
      (node (ref "RN13") (pin "3") (pinfunction "3_3") (pintype "passive"))
      (node (ref "RN13") (pin "4") (pinfunction "4_4") (pintype "passive"))
      (node (ref "RN14") (pin "1") (pinfunction "1_1") (pintype "passive"))
      (node (ref "RN14") (pin "2") (pinfunction "2_2") (pintype "passive"))
      (node (ref "RN14") (pin "3") (pinfunction "3_3") (pintype "passive"))
      (node (ref "RN14") (pin "4") (pinfunction "4_4") (pintype "passive"))
      (node (ref "RN15") (pin "1") (pinfunction "1_1") (pintype "passive"))
      (node (ref "RN15") (pin "2") (pinfunction "2_2") (pintype "passive"))
      (node (ref "RN15") (pin "3") (pinfunction "3_3") (pintype "passive"))
      (node (ref "RN15") (pin "4") (pinfunction "4_4") (pintype "passive"))
    )
    (net (code "77") (name "VTT_REF") (class "Default")
      (node (ref "C71") (pin "2") (pinfunction "2_2") (pintype "passive"))
      (node (ref "C72") (pin "1") (pinfunction "1_1") (pintype "passive"))
      (node (ref "C73") (pin "1") (pinfunction "1_1") (pintype "passive"))
      (node (ref "C74") (pin "2") (pinfunction "2_2") (pintype "passive"))
      (node (ref "C75") (pin "1") (pinfunction "1_1") (pintype "passive"))
      (node (ref "C76") (pin "1") (pinfunction "1_1") (pintype "passive"))
      (node (ref "IC20") (pin "H1") (pinfunction "VREFDQ_H1") (pintype "power_in"))
      (node (ref "IC20") (pin "M8") (pinfunction "VREFCA_M8") (pintype "power_in"))
      (node (ref "IC21") (pin "H1") (pinfunction "VREFDQ_H1") (pintype "power_in"))
      (node (ref "IC21") (pin "M8") (pinfunction "VREFCA_M8") (pintype "power_in"))
    )
    (net (code "78") (name "unconnected-(IC20-NC-PadJ1)") (class "Default")
      (node (ref "IC20") (pin "J1") (pinfunction "NC_J1") (pintype "passive+no_connect"))
    )
    (net (code "79") (name "unconnected-(IC20-NC-PadJ9)") (class "Default")
      (node (ref "IC20") (pin "J9") (pinfunction "NC_J9") (pintype "passive+no_connect"))
    )
    (net (code "80") (name "unconnected-(IC20-NC-PadL1)") (class "Default")
      (node (ref "IC20") (pin "L1") (pinfunction "NC_L1") (pintype "passive+no_connect"))
    )
    (net (code "81") (name "unconnected-(IC20-NC-PadL9)") (class "Default")
      (node (ref "IC20") (pin "L9") (pinfunction "NC_L9") (pintype "passive+no_connect"))
    )
    (net (code "82") (name "unconnected-(IC20-NC-PadM7)") (class "Default")
      (node (ref "IC20") (pin "M7") (pinfunction "NC_M7") (pintype "passive+no_connect"))
    )
    (net (code "83") (name "unconnected-(IC20-NC-PadT7)") (class "Default")
      (node (ref "IC20") (pin "T7") (pinfunction "NC_T7") (pintype "passive+no_connect"))
    )
    (net (code "84") (name "unconnected-(IC21-NC-PadJ1)") (class "Default")
      (node (ref "IC21") (pin "J1") (pinfunction "NC_J1") (pintype "passive+no_connect"))
    )
    (net (code "85") (name "unconnected-(IC21-NC-PadJ9)") (class "Default")
      (node (ref "IC21") (pin "J9") (pinfunction "NC_J9") (pintype "passive+no_connect"))
    )
    (net (code "86") (name "unconnected-(IC21-NC-PadL1)") (class "Default")
      (node (ref "IC21") (pin "L1") (pinfunction "NC_L1") (pintype "passive+no_connect"))
    )
    (net (code "87") (name "unconnected-(IC21-NC-PadL9)") (class "Default")
      (node (ref "IC21") (pin "L9") (pinfunction "NC_L9") (pintype "passive+no_connect"))
    )
    (net (code "88") (name "unconnected-(IC21-NC-PadM7)") (class "Default")
      (node (ref "IC21") (pin "M7") (pinfunction "NC_M7") (pintype "passive+no_connect"))
    )
    (net (code "89") (name "unconnected-(IC21-NC-PadT7)") (class "Default")
      (node (ref "IC21") (pin "T7") (pinfunction "NC_T7") (pintype "passive+no_connect"))
    )
    (net (code "90") (name "unconnected-(RN11-Pad4)") (class "Default")
      (node (ref "RN11") (pin "4") (pinfunction "4_4") (pintype "passive"))
    )
    (net (code "91") (name "unconnected-(RN11-Pad5)") (class "Default")
      (node (ref "RN11") (pin "5") (pinfunction "5_5") (pintype "passive"))
    )
  )
)
